# ECR_Schem_1.net
KiCad netlist of a schematic drawn in Altium Designer
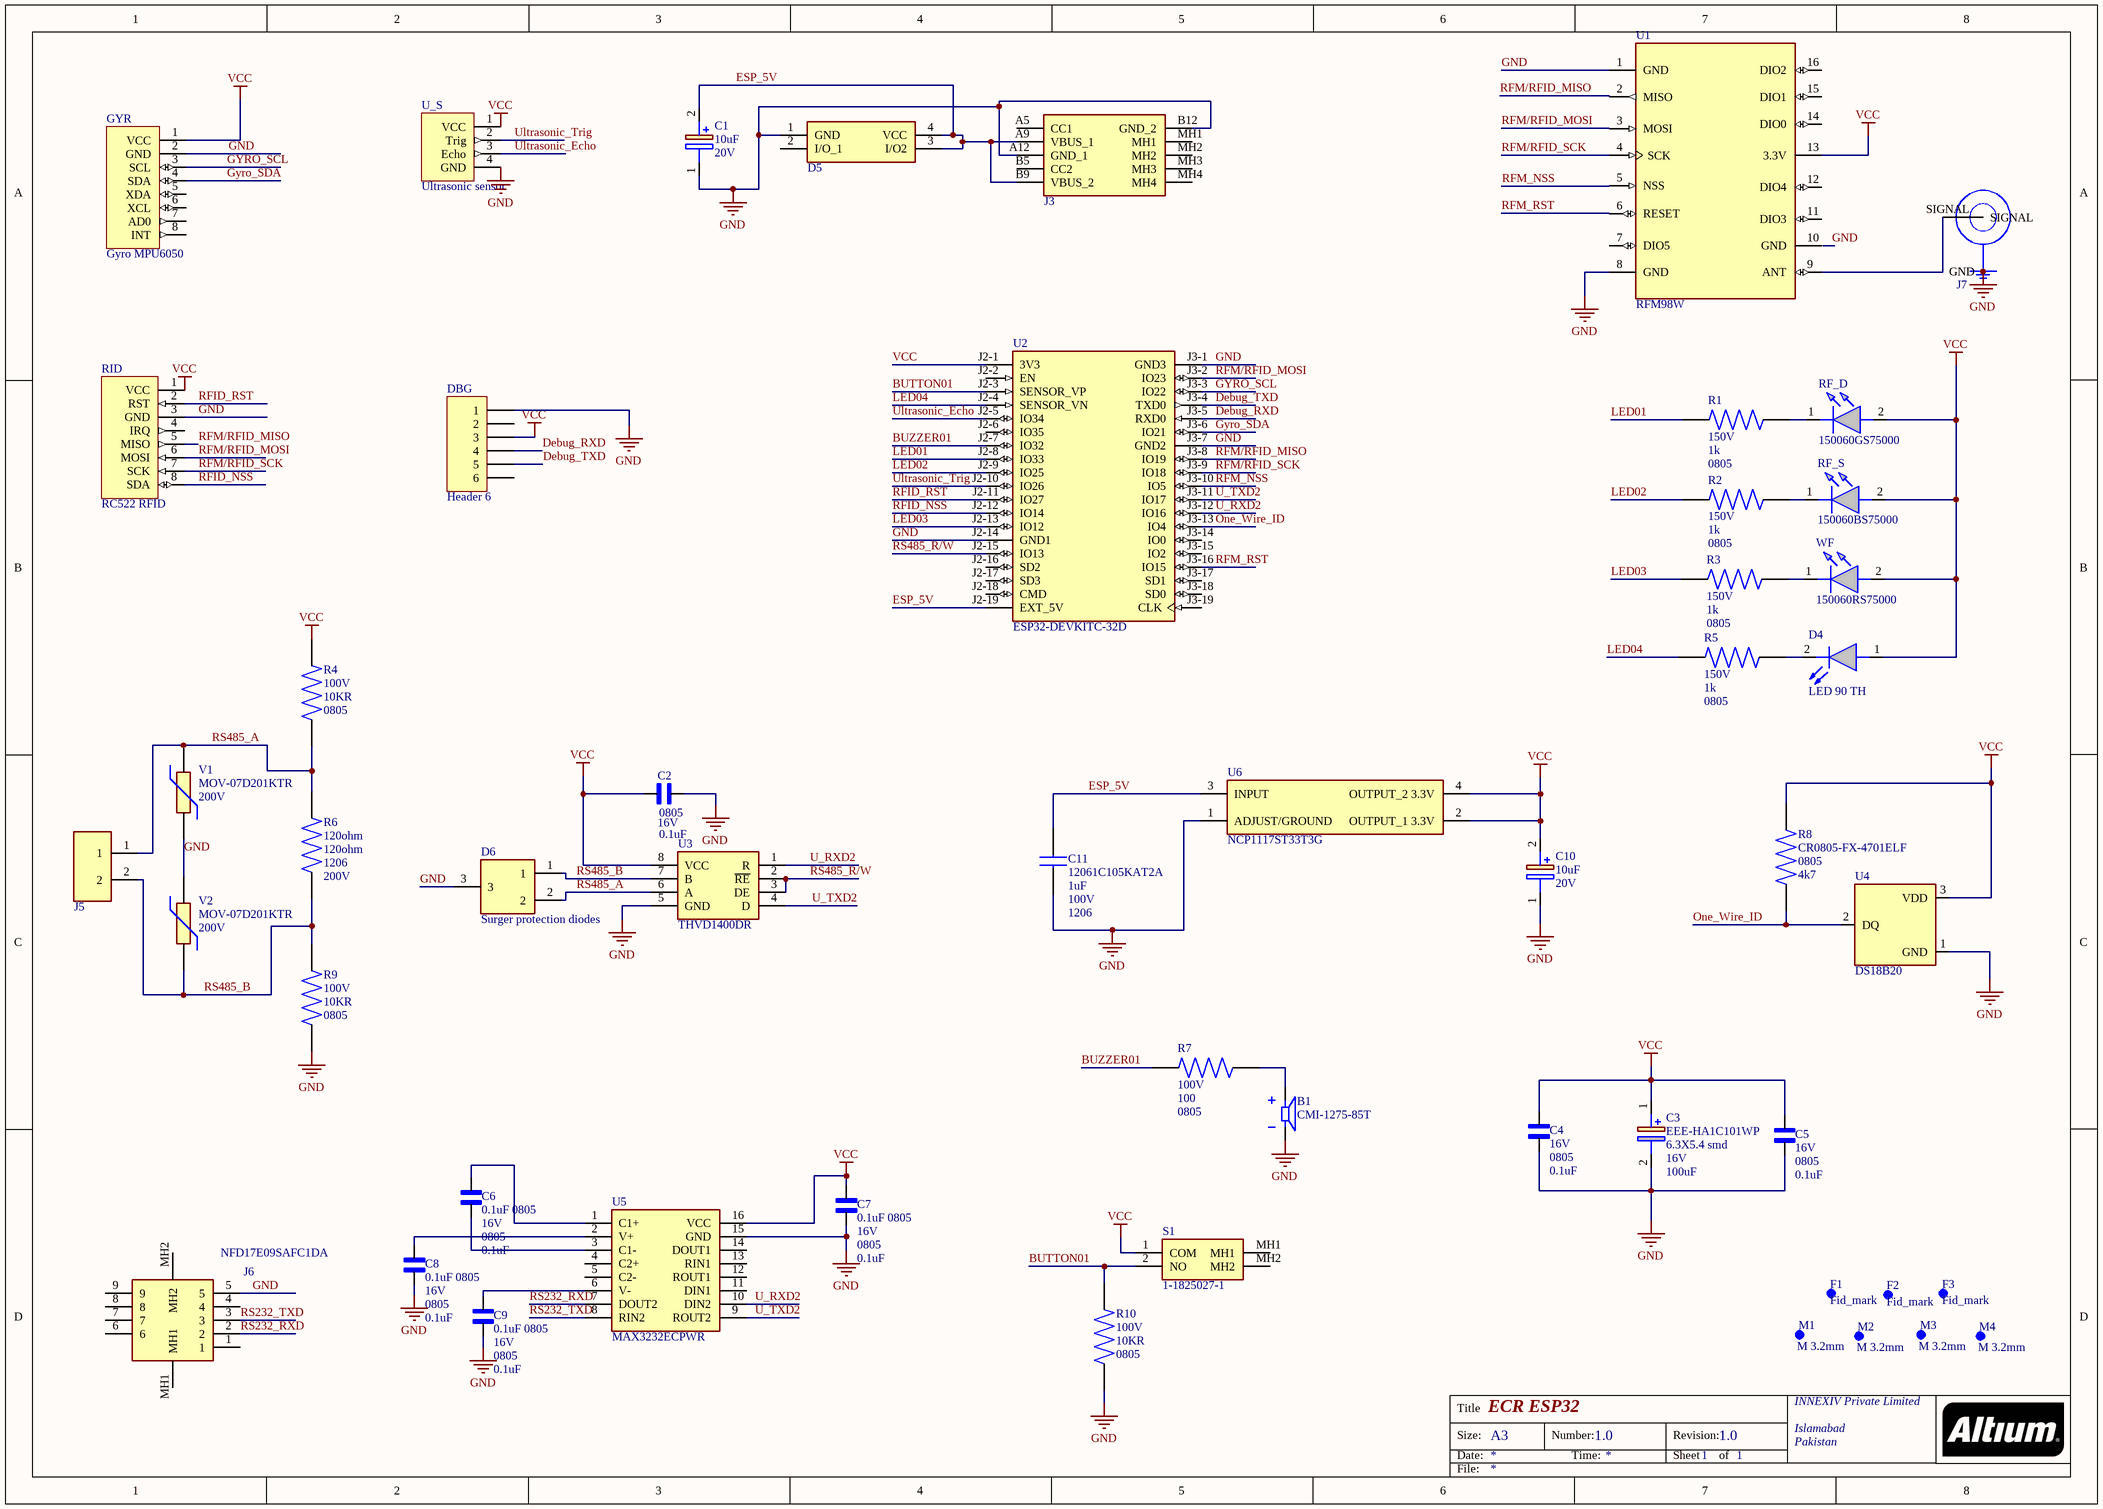
[diagram p0: ECR_Schem_1.SchDoc]

(export (version "E")
  (design (tool "Eeschema 10.0.6"))
  (components
    (comp (ref "B1")
      (value "CMI-1275-85T")
      (footprint "CUI_CMI-1275-85T")
      (description "5V CUI Inc Buzzer")
      (libsource (lib "CMI-1275-85T") (part "CMI-1275-85T"))
    )
    (comp (ref "C1")
      (value "10uF")
      (footprint "CAPPM3528X210N")
      (fields
        (field (name "MANUFACTURER_PART_NUMBER") "TPSB106K020R1000")
        (field (name "MOUSER PART NUMBER") "581-TPSB106K020R1000")
        (field (name "VOLTAGE") "20V")
        (field (name "Comment") "10uF SMD Tantalum")
      )
      (libsource (lib "ECR") (part "TPSB106K020R1000"))
    )
    (comp (ref "C2")
      (value "0.1uF")
      (footprint "CAPC2012X90N")
      (description "Cap Ceramic 0.1uF 16V X7R 5% SMD 0805 125Â°C Paper T/R")
      (fields
        (field (name "MF") "Vishay Vitramon")
        (field (name "MP") "VJ0805Y104JXJPW1BC")
        (field (name "VOLTAGE") "16V")
        (field (name "PACKAGE") "0805")
      )
      (libsource (lib "") (part "VJ0805Y104JXJPW1BC_1"))
    )
    (comp (ref "C3")
      (value "EEE-HA1C101WP")
      (footprint "CAPAE660X800N")
      (description "Cap Aluminum Lytic 100uF 16V 20% (6.3 X 5.4mm) SMD 70mA 1000h 105C Automotive T/R")
      (fields
        (field (name "PACKAGE") "6.3X5.4 smd")
        (field (name "VOLTAGE") "16V")
        (field (name "ALTIUM_VALUE") "100uF")
      )
      (libsource (lib "ECR") (part "EEE-HA1C101WP"))
    )
    (comp (ref "C4")
      (value "0.1uF")
      (footprint "CAPC2012X90N")
      (description "Cap Ceramic 0.1uF 16V X7R 5% SMD 0805 125Â°C Paper T/R")
      (fields
        (field (name "MF") "Vishay Vitramon")
        (field (name "MP") "VJ0805Y104JXJPW1BC")
        (field (name "VOLTAGE") "16V")
        (field (name "PACKAGE") "0805")
      )
      (libsource (lib "ECR") (part "VJ0805Y104JXJPW1BC"))
    )
    (comp (ref "C5")
      (value "0.1uF")
      (footprint "CAPC2012X90N")
      (description "Cap Ceramic 0.1uF 16V X7R 5% SMD 0805 125Â°C Paper T/R")
      (fields
        (field (name "MF") "Vishay Vitramon")
        (field (name "MP") "VJ0805Y104JXJPW1BC")
        (field (name "VOLTAGE") "16V")
        (field (name "PACKAGE") "0805")
      )
      (libsource (lib "ECR") (part "VJ0805Y104JXJPW1BC"))
    )
    (comp (ref "C6")
      (value "0.1uF 0805")
      (footprint "CAPC2012X90N")
      (description "Cap Ceramic 0.1uF 16V X7R 5% SMD 0805 125Â°C Paper T/R")
      (fields
        (field (name "MF") "Vishay Vitramon")
        (field (name "MP") "VJ0805Y104JXJPW1BC")
        (field (name "VOLTAGE") "16V")
        (field (name "PACKAGE") "0805")
        (field (name "ALTIUM_VALUE") "0.1uF")
      )
      (libsource (lib "ECR") (part "VJ0805Y104JXJPW1BC"))
    )
    (comp (ref "C7")
      (value "0.1uF 0805")
      (footprint "CAPC2012X90N")
      (description "Cap Ceramic 0.1uF 16V X7R 5% SMD 0805 125Â°C Paper T/R")
      (fields
        (field (name "MF") "Vishay Vitramon")
        (field (name "MP") "VJ0805Y104JXJPW1BC")
        (field (name "VOLTAGE") "16V")
        (field (name "PACKAGE") "0805")
        (field (name "ALTIUM_VALUE") "0.1uF")
      )
      (libsource (lib "ECR") (part "VJ0805Y104JXJPW1BC"))
    )
    (comp (ref "C8")
      (value "0.1uF 0805")
      (footprint "CAPC2012X90N")
      (description "Cap Ceramic 0.1uF 16V X7R 5% SMD 0805 125Â°C Paper T/R")
      (fields
        (field (name "MF") "Vishay Vitramon")
        (field (name "MP") "VJ0805Y104JXJPW1BC")
        (field (name "VOLTAGE") "16V")
        (field (name "PACKAGE") "0805")
        (field (name "ALTIUM_VALUE") "0.1uF")
      )
      (libsource (lib "ECR") (part "VJ0805Y104JXJPW1BC"))
    )
    (comp (ref "C9")
      (value "0.1uF 0805")
      (footprint "CAPC2012X90N")
      (description "Cap Ceramic 0.1uF 16V X7R 5% SMD 0805 125Â°C Paper T/R")
      (fields
        (field (name "MF") "Vishay Vitramon")
        (field (name "MP") "VJ0805Y104JXJPW1BC")
        (field (name "VOLTAGE") "16V")
        (field (name "PACKAGE") "0805")
        (field (name "ALTIUM_VALUE") "0.1uF")
      )
      (libsource (lib "ECR") (part "VJ0805Y104JXJPW1BC"))
    )
    (comp (ref "C10")
      (value "10uF")
      (footprint "CAPPM3528X210N")
      (fields
        (field (name "MANUFACTURER_PART_NUMBER") "TPSB106K020R1000")
        (field (name "MOUSER PART NUMBER") "581-TPSB106K020R1000")
        (field (name "VOLTAGE") "20V")
        (field (name "Comment") "10uF SMD Tantalum")
      )
      (libsource (lib "ECR") (part "TPSB106K020R1000"))
    )
    (comp (ref "C11")
      (value "12061C105KAT2A")
      (footprint "CAPC3216X229N")
      (fields
        (field (name "MOUSER PART NUMBER") "581-12061C105KAT2A")
        (field (name "ALTIUM_VALUE") "1uF")
        (field (name "VOLTAGE") "100V")
        (field (name "PACKAGE") "1206")
      )
      (libsource (lib "12061C105KAT2A") (part "12061C105KAT2A"))
    )
    (comp (ref "D4")
      (value "LED 90 TH")
      (footprint "HV-31210/260/SUB-U1930")
      (description "HARVATEK 3.0MM ROUND LED LAMP WI")
      (libsource (lib "ECR") (part "HV-31210/260/SUB-U1930"))
    )
    (comp (ref "D5")
      (value "5V fuse USB line")
      (footprint "SR0502CTG")
      (description "LITTELFUSE - SR05-02CTG - DIODE, ESD PROTECTION, 5V, SOT-143")
      (fields
        (field (name "MANUFACTURER_PART_NUMBER") "SR05-02CTG")
        (field (name "MOUSER PART NUMBER") "576-SR05-02CTG")
      )
      (libsource (lib "ECR") (part "SR05-02CTG"))
    )
    (comp (ref "D6")
      (value "Surger protection diodes")
      (footprint "SamacSys:SOT95P230X117-3N")
      (description "Diode")
      (fields
        (field (name "MANUFACTURER_PART_NUMBER") "CDSOT23-SM712")
        (field (name "MOUSER PART NUMBER") "652-CDSOT23-SM712")
      )
      (libsource (lib "ECR") (part "CDSOT23-SM712"))
    )
    (comp (ref "DBG")
      (value "Header 6")
      (footprint "HDR1X6")
      (description "Header, 6-Pin")
      (fields (field (name "PUBLISHER") "Altium Limited"))
      (libsource (lib "Miscellaneous Connectors") (part "Header 6"))
    )
    (comp (ref "F1")
      (value "Fid_mark")
      (footprint "FUP")
      (description "Fiducial_mark")
      (libsource (lib "ECR") (part "Fid_mark"))
    )
    (comp (ref "F2")
      (value "Fid_mark")
      (footprint "FUP")
      (description "Fiducial_mark")
      (libsource (lib "ECR") (part "Fid_mark"))
    )
    (comp (ref "F3")
      (value "Fid_mark")
      (footprint "FUP")
      (description "Fiducial_mark")
      (libsource (lib "ECR") (part "Fid_mark"))
    )
    (comp (ref "GYR")
      (value "Gyro MPU6050")
      (footprint "MPU_8pin")
      (description "MPU_6050\r\nGyroscope")
      (libsource (lib "ECR") (part "MPU_6050"))
    )
    (comp (ref "J3")
      (value "USB Type C PCB")
      (footprint "USB4125GFA")
      (fields
        (field (name "MANUFACTURER_PART_NUMBER") "USB4125-GF-A")
        (field (name "MOUSER PART NUMBER") "640-USB4125-GF-A")
      )
      (libsource (lib "ECR") (part "USB4125-GF-A"))
    )
    (comp (ref "J5")
      (value "3.81mm wire to pcb")
      (footprint "1728284 3.81 wire to pcb")
      (description "TERM BLOCK 2POS 55DEG 3.81MM PCB")
      (fields (field (name "MANUFACTURER") "Phoenix contact"))
      (libsource (lib "ECR") (part "1728284 terminal block 3.81"))
    )
    (comp (ref "J6")
      (value "NFD17E09SAFC1DA")
      (footprint "NFD17E09SAFC1DA")
      (description "D-Sub, 9 Pin Socket, Right Angle, Boardlocks #4-40 UNC Threaded Hole")
      (libsource (lib "NFD17E09SAFC1DA") (part "NFD17E09SAFC1DA"))
    )
    (comp (ref "J7")
      (value "IPEX antenna connector PCB")
      (footprint "AMPHENOL_A-1JB")
      (description "AMC IPEX Straight PCB Jack, Surface Mount, 2500 pc Reel, 50 Ohm")
      (fields (field (name "MP") "A-1JB"))
      (libsource (lib "A-1JB") (part "A-1JB"))
    )
    (comp (ref "M1")
      (value "M 3.2mm")
      (footprint "Screw Hole 3.2mm")
      (description "PCB Munting Hole 3.2mm")
      (libsource (lib "ECR") (part "Munting Hole 3.2mm"))
    )
    (comp (ref "M2")
      (value "M 3.2mm")
      (footprint "Screw Hole 3.2mm")
      (description "PCB Munting Hole 3.2mm")
      (libsource (lib "ECR") (part "Munting Hole 3.2mm"))
    )
    (comp (ref "M3")
      (value "M 3.2mm")
      (footprint "Screw Hole 3.2mm")
      (description "PCB Munting Hole 3.2mm")
      (libsource (lib "ECR") (part "Munting Hole 3.2mm"))
    )
    (comp (ref "M4")
      (value "M 3.2mm")
      (footprint "Screw Hole 3.2mm")
      (description "PCB Munting Hole 3.2mm")
      (libsource (lib "ECR") (part "Munting Hole 3.2mm"))
    )
    (comp (ref "R1")
      (value "1k")
      (footprint "0805_RESC2012X50N")
      (description "Thick Film Resistors - SMD 1 k Ohms 125mW 0805 5% AEC-Q200 Standard Power Version")
      (fields
        (field (name "MF") "{'manufacturer': u'Bourns'}")
        (field (name "MP") "AC0805JR-071KL")
        (field (name "VOLTAGE") "150V")
        (field (name "PACKAGE") "0805")
      )
      (libsource (lib "ECR") (part "AC0805JR-071KL"))
    )
    (comp (ref "R2")
      (value "1k")
      (footprint "0805_RESC2012X50N")
      (description "Thick Film Resistors - SMD 1 k Ohms 125mW 0805 5% AEC-Q200 Standard Power Version")
      (fields
        (field (name "MF") "{'manufacturer': u'Bourns'}")
        (field (name "MP") "AC0805JR-071KL")
        (field (name "VOLTAGE") "150V")
        (field (name "PACKAGE") "0805")
      )
      (libsource (lib "ECR") (part "AC0805JR-071KL"))
    )
    (comp (ref "R3")
      (value "1k")
      (footprint "0805_RESC2012X50N")
      (description "Thick Film Resistors - SMD 1 k Ohms 125mW 0805 5% AEC-Q200 Standard Power Version")
      (fields
        (field (name "MF") "{'manufacturer': u'Bourns'}")
        (field (name "MP") "AC0805JR-071KL")
        (field (name "VOLTAGE") "150V")
        (field (name "PACKAGE") "0805")
      )
      (libsource (lib "ECR") (part "AC0805JR-071KL"))
    )
    (comp (ref "R4")
      (value "10KR")
      (footprint "0805_RESC2012X50N")
      (fields
        (field (name "MF") "{'manufacturer': u'Bourns'}")
        (field (name "MP") "CR0805-FX-1002ELF")
        (field (name "VOLTAGE") "100V")
        (field (name "PACKAGE") "0805")
        (field (name "Comment") "10K 0805")
      )
      (libsource (lib "ECR") (part "CR0805-FX-1002ELF"))
    )
    (comp (ref "R5")
      (value "1k")
      (footprint "0805_RESC2012X50N")
      (description "Thick Film Resistors - SMD 1 k Ohms 125mW 0805 5% AEC-Q200 Standard Power Version")
      (fields
        (field (name "MF") "{'manufacturer': u'Bourns'}")
        (field (name "MP") "AC0805JR-071KL")
        (field (name "VOLTAGE") "150V")
        (field (name "PACKAGE") "0805")
      )
      (libsource (lib "ECR") (part "AC0805JR-071KL"))
    )
    (comp (ref "R6")
      (value "120ohm")
      (footprint "1206_RESC3216X06N")
      (description "RES 120 OHM 5% 1/4W 1206")
      (fields
        (field (name "PART NUMBER") "WR12X1002FTL")
        (field (name "ALTIUM_VALUE") "120ohm")
        (field (name "PACKAGE") "1206")
        (field (name "VOLTAGE") "200V")
      )
      (libsource (lib "ECR") (part "WR12X1002FTL"))
    )
    (comp (ref "R7")
      (value "100")
      (footprint "0805_RESC2012X50N")
      (description "Thick Film Resistors - SMD 0805 100ohms 0.5W 5% Tolerance")
      (fields
        (field (name "MF") "{'manufacturer': u'Bourns'}")
        (field (name "MP") "ERJ-P06J101V")
        (field (name "VOLTAGE") "100V")
        (field (name "PACKAGE") "0805")
      )
      (libsource (lib "ECR") (part "ERJ-P06J101V"))
    )
    (comp (ref "R8")
      (value "CR0805-FX-4701ELF")
      (footprint "0805_RESC2012X50N")
      (description "BOURNS - CR0805-FX-4701ELF - RES, THICK FILM, 4K7, 1%, 0.125W, 0805")
      (fields
        (field (name "MOUSER PART NUMBER") "652-CR0805FX-4701ELF")
        (field (name "PACKAGE") "0805")
        (field (name "ALTIUM_VALUE") "4k7")
      )
      (libsource (lib "ECR") (part "CR0805-FX-4701ELF"))
    )
    (comp (ref "R9")
      (value "10KR")
      (footprint "0805_RESC2012X50N")
      (fields
        (field (name "MF") "{'manufacturer': u'Bourns'}")
        (field (name "MP") "CR0805-FX-1002ELF")
        (field (name "VOLTAGE") "100V")
        (field (name "PACKAGE") "0805")
        (field (name "Comment") "10K 0805")
      )
      (libsource (lib "ECR") (part "CR0805-FX-1002ELF"))
    )
    (comp (ref "R10")
      (value "10KR")
      (footprint "0805_RESC2012X50N")
      (fields
        (field (name "MF") "{'manufacturer': u'Bourns'}")
        (field (name "MP") "CR0805-FX-1002ELF")
        (field (name "VOLTAGE") "100V")
        (field (name "PACKAGE") "0805")
        (field (name "Comment") "10K 0805")
      )
      (libsource (lib "ECR") (part "CR0805-FX-1002ELF"))
    )
    (comp (ref "RF_D")
      (value "150060GS75000")
      (footprint "LEDC1608X80N")
      (description "Wurth Elektronik WL-SMCW 520 nm Green LED, 1608 (0603) Clear SMD package")
      (fields (field (name "MOUSER PART NUMBER") "710-150060GS75000"))
      (libsource (lib "150060GS75000") (part "150060GS75000"))
    )
    (comp (ref "RF_S")
      (value "150060BS75000")
      (footprint "LEDC1608X80N")
      (fields (field (name "MOUSER PART NUMBER") "710-150060BS75000"))
      (libsource (lib "150060BS75000") (part "150060BS75000"))
    )
    (comp (ref "RID")
      (value "RC522 RFID")
      (footprint "RFID_8pin")
      (description "RFID card reader")
      (libsource (lib "ECR") (part "RFID-RC522"))
    )
    (comp (ref "S1")
      (value "1-1825027-1")
      (footprint "118250271")
      (description "Black Button Tactile Switch, Single Pole Single Throw (SPST) 50 mA @ 24 V dc 5.74mm")
      (libsource (lib "1-1825027-1") (part "1-1825027-1"))
    )
    (comp (ref "U1")
      (value "RFM98W")
      (footprint "XCVR_RFM98W-433S2")
      (description "802.15.4, General ISM < 1GHz LoRaâ„¢ Transceiver Module 433MHz Surface Mount")
      (fields (field (name "MF") "RF Solutions") (field (name "MP") "RFM98W-433S2"))
      (libsource (lib "RFM98W") (part "RFM98W"))
    )
    (comp (ref "U2")
      (value "ESP32-DEVKITC-32D")
      (footprint "MODULE_ESP32-DEVKITC-32D")
      (description "WiFi Development Tools (802.11) ESP32 General Development Kit, ESP32-WROOM-32D on the board")
      (fields (field (name "MF") "Espressif Systems"))
      (libsource (lib "ESP32-DEVKITC-32D") (part "ESP32-DEVKITC-32D"))
    )
    (comp (ref "U3")
      (value "THVD1400DR")
      (footprint "SOIC127P600X175-8N")
      (fields (field (name "MOUSER PART NUMBER") "595-THVD1400DR"))
      (libsource (lib "THVD1400DR") (part "THVD1400DR"))
    )
    (comp (ref "U4")
      (value "DS18B20")
      (footprint "TO-92-TO92127P495H2044-3")
      (description "Temperature Sensor Digital, Local -55Â°C ~ 125Â°C 12 b 8-uMAX-EP¦8-uSOP-EP")
      (fields (field (name "MF") "Maxim"))
      (libsource (lib "DS18B20") (part "DS18B20"))
    )
    (comp (ref "U5")
      (value "MAX3232ECPWR")
      (footprint "SOP65P640X120-16N")
      (description "3-V to 5.5-V multichannel RS-232 line driver and receiver with +/-15-kV IEC ESD protection")
      (fields (field (name "MOUSER PART NUMBER") "595-MAX3232ECPWR"))
      (libsource (lib "MAX3232ECPWR") (part "MAX3232ECPWR"))
    )
    (comp (ref "U6")
      (value "NCP1117ST33T3G")
      (footprint "SOT230P700X180-4N")
      (description "ON SEMICONDUCTOR - NCP1117ST33T3G - IC, LINEAR VOLTAGE REGULATOR")
      (fields (field (name "MOUSER PART NUMBER") "863-NCP1117ST33T3G"))
      (libsource (lib "NCP1117ST33T3G") (part "NCP1117ST33T3G"))
    )
    (comp (ref "U_S")
      (value "Ultrasonic sensor")
      (footprint "UltraSonic 4 Pins")
      (description "Hc Sr04 Arduino Ultrasonic Sensor")
      (libsource (lib "ECR") (part "HC-SR04"))
    )
    (comp (ref "V1")
      (value "MOV-07D201KTR")
      (footprint "MOV07D201KTR")
      (description "VARISTOR 200V 1.2KA DISC 7MM")
      (fields (field (name "MOUSER PART NUMBER") "652-MOV-07D201KTR") (field (name "VOLTAGE") "200V"))
      (libsource (lib "ECR") (part "MOV-07D201KTR"))
    )
    (comp (ref "V2")
      (value "MOV-07D201KTR")
      (footprint "MOV07D201KTR")
      (description "VARISTOR 200V 1.2KA DISC 7MM")
      (fields (field (name "MOUSER PART NUMBER") "652-MOV-07D201KTR") (field (name "VOLTAGE") "200V"))
      (libsource (lib "ECR") (part "MOV-07D201KTR"))
    )
    (comp (ref "WF")
      (value "150060RS75000")
      (footprint "LEDC1608X80N")
      (description "WURTH ELEKTRONIK - 150060RS75000 - LED, 0603, RED, 250MCD, 625NM")
      (fields (field (name "MOUSER PART NUMBER") "710-150060RS75000"))
      (libsource (lib "150060RS75000") (part "150060RS75000"))
    )
  )
  (nets
    (net (code "1") (name "/BUTTON01") (class "Default")
      (node (ref "R10") (pin "2") (pinfunction "2_2") (pintype "passive"))
      (node (ref "S1") (pin "2") (pinfunction "NO_2") (pintype "passive"))
      (node (ref "U2") (pin "J2-3") (pinfunction "SENSOR_VP_J2-3") (pintype "input"))
    )
    (net (code "2") (name "/BUZZER01") (class "Default")
      (node (ref "R7") (pin "1") (pinfunction "1_1") (pintype "passive"))
      (node (ref "U2") (pin "J2-7") (pinfunction "IO32_J2-7") (pintype "bidirectional"))
    )
    (net (code "3") (name "/Debug_RXD") (class "Default")
      (node (ref "DBG") (pin "4") (pinfunction "4_4") (pintype "passive"))
      (node (ref "U2") (pin "J3-5") (pinfunction "RXD0_J3-5") (pintype "input"))
    )
    (net (code "4") (name "/Debug_TXD") (class "Default")
      (node (ref "DBG") (pin "5") (pinfunction "5_5") (pintype "passive"))
      (node (ref "U2") (pin "J3-4") (pinfunction "TXD0_J3-4") (pintype "output"))
    )
    (net (code "5") (name "/ESP_5V") (class "Default")
      (node (ref "C1") (pin "2") (pinfunction "2_2") (pintype "passive"))
      (node (ref "C11") (pin "2") (pinfunction "2_2") (pintype "passive"))
      (node (ref "D5") (pin "3") (pinfunction "I/O2_3") (pintype "passive"))
      (node (ref "D5") (pin "4") (pinfunction "VCC_4") (pintype "passive"))
      (node (ref "J3") (pin "A9") (pinfunction "VBUS_1_A9") (pintype "passive"))
      (node (ref "J3") (pin "B9") (pinfunction "VBUS_2_B9") (pintype "passive"))
      (node (ref "U2") (pin "J2-19") (pinfunction "EXT_5V_J2-19") (pintype "power_in"))
      (node (ref "U6") (pin "3") (pinfunction "INPUT_3") (pintype "passive"))
    )
    (net (code "6") (name "/GYRO_SCL") (class "Default")
      (node (ref "GYR") (pin "3") (pinfunction "SCL_3") (pintype "bidirectional"))
      (node (ref "U2") (pin "J3-3") (pinfunction "IO22_J3-3") (pintype "bidirectional"))
    )
    (net (code "7") (name "/Gyro_SDA") (class "Default")
      (node (ref "GYR") (pin "4") (pinfunction "SDA_4") (pintype "bidirectional"))
      (node (ref "U2") (pin "J3-6") (pinfunction "IO21_J3-6") (pintype "bidirectional"))
    )
    (net (code "8") (name "/LED01") (class "Default")
      (node (ref "R1") (pin "1") (pinfunction "1_1") (pintype "passive"))
      (node (ref "U2") (pin "J2-8") (pinfunction "IO33_J2-8") (pintype "bidirectional"))
    )
    (net (code "9") (name "/LED02") (class "Default")
      (node (ref "R2") (pin "1") (pinfunction "1_1") (pintype "passive"))
      (node (ref "U2") (pin "J2-9") (pinfunction "IO25_J2-9") (pintype "bidirectional"))
    )
    (net (code "10") (name "/LED03") (class "Default")
      (node (ref "R3") (pin "1") (pinfunction "1_1") (pintype "passive"))
      (node (ref "U2") (pin "J2-13") (pinfunction "IO12_J2-13") (pintype "bidirectional"))
    )
    (net (code "11") (name "/LED04") (class "Default")
      (node (ref "R5") (pin "1") (pinfunction "1_1") (pintype "passive"))
      (node (ref "U2") (pin "J2-4") (pinfunction "SENSOR_VN_J2-4") (pintype "input"))
    )
    (net (code "12") (name "/One_Wire_ID") (class "Default")
      (node (ref "R8") (pin "1") (pinfunction "1_1") (pintype "passive"))
      (node (ref "U2") (pin "J3-13") (pinfunction "IO4_J3-13") (pintype "bidirectional"))
      (node (ref "U4") (pin "2") (pinfunction "DQ_2") (pintype "bidirectional"))
    )
    (net (code "13") (name "/RFID_NSS") (class "Default")
      (node (ref "RID") (pin "8") (pinfunction "SDA_8") (pintype "bidirectional"))
      (node (ref "U2") (pin "J2-12") (pinfunction "IO14_J2-12") (pintype "bidirectional"))
    )
    (net (code "14") (name "/RFID_RST") (class "Default")
      (node (ref "RID") (pin "2") (pinfunction "RST_2") (pintype "input"))
      (node (ref "U2") (pin "J2-11") (pinfunction "IO27_J2-11") (pintype "bidirectional"))
    )
    (net (code "15") (name "/RFM_NSS") (class "Default")
      (node (ref "U1") (pin "5") (pinfunction "NSS_5") (pintype "input"))
      (node (ref "U2") (pin "J3-10") (pinfunction "IO5_J3-10") (pintype "bidirectional"))
    )
    (net (code "16") (name "/RFM_RST") (class "Default")
      (node (ref "U1") (pin "6") (pinfunction "RESET_6") (pintype "bidirectional"))
      (node (ref "U2") (pin "J3-16") (pinfunction "IO15_J3-16") (pintype "bidirectional"))
    )
    (net (code "17") (name "/RFM{slash}RFID_MISO") (class "Default")
      (node (ref "RID") (pin "5") (pinfunction "MISO_5") (pintype "output"))
      (node (ref "U1") (pin "2") (pinfunction "MISO_2") (pintype "output"))
      (node (ref "U2") (pin "J3-8") (pinfunction "IO19_J3-8") (pintype "bidirectional"))
    )
    (net (code "18") (name "/RFM{slash}RFID_MOSI") (class "Default")
      (node (ref "RID") (pin "6") (pinfunction "MOSI_6") (pintype "input"))
      (node (ref "U1") (pin "3") (pinfunction "MOSI_3") (pintype "input"))
      (node (ref "U2") (pin "J3-2") (pinfunction "IO23_J3-2") (pintype "bidirectional"))
    )
    (net (code "19") (name "/RFM{slash}RFID_SCK") (class "Default")
      (node (ref "RID") (pin "7") (pinfunction "SCK_7") (pintype "input"))
      (node (ref "U1") (pin "4") (pinfunction "SCK_4") (pintype "input"))
      (node (ref "U2") (pin "J3-9") (pinfunction "IO18_J3-9") (pintype "bidirectional"))
    )
    (net (code "20") (name "/RS232_RXD") (class "Default")
      (node (ref "J6") (pin "2") (pinfunction "2_2") (pintype "passive"))
      (node (ref "U5") (pin "7") (pinfunction "DOUT2_7") (pintype "passive"))
    )
    (net (code "21") (name "/RS232_TXD") (class "Default")
      (node (ref "J6") (pin "3") (pinfunction "3_3") (pintype "passive"))
      (node (ref "U5") (pin "8") (pinfunction "RIN2_8") (pintype "passive"))
    )
    (net (code "22") (name "/RS485_A") (class "Default")
      (node (ref "D6") (pin "2") (pinfunction "2_2") (pintype "passive"))
      (node (ref "J5") (pin "1") (pinfunction "1_1") (pintype "passive"))
      (node (ref "R4") (pin "1") (pinfunction "1_1") (pintype "passive"))
      (node (ref "R6") (pin "2") (pinfunction "2_2") (pintype "passive"))
      (node (ref "U3") (pin "6") (pinfunction "A_6") (pintype "passive"))
      (node (ref "V1") (pin "2") (pinfunction "2_2") (pintype "passive"))
    )
    (net (code "23") (name "/RS485_B") (class "Default")
      (node (ref "D6") (pin "1") (pinfunction "1_1") (pintype "passive"))
      (node (ref "J5") (pin "2") (pinfunction "2_2") (pintype "passive"))
      (node (ref "R6") (pin "1") (pinfunction "1_1") (pintype "passive"))
      (node (ref "R9") (pin "2") (pinfunction "2_2") (pintype "passive"))
      (node (ref "U3") (pin "7") (pinfunction "B_7") (pintype "passive"))
      (node (ref "V2") (pin "1") (pinfunction "1_1") (pintype "passive"))
    )
    (net (code "24") (name "/RS485_R{slash}W") (class "Default")
      (node (ref "U2") (pin "J2-15") (pinfunction "IO13_J2-15") (pintype "bidirectional"))
      (node (ref "U3") (pin "2") (pinfunction "~{RE}_2") (pintype "passive"))
      (node (ref "U3") (pin "3") (pinfunction "DE_3") (pintype "passive"))
    )
    (net (code "25") (name "/U_RXD2") (class "Default")
      (node (ref "U2") (pin "J3-12") (pinfunction "IO16_J3-12") (pintype "bidirectional"))
      (node (ref "U3") (pin "1") (pinfunction "R_1") (pintype "passive"))
      (node (ref "U5") (pin "10") (pinfunction "DIN2_10") (pintype "passive"))
    )
    (net (code "26") (name "/U_TXD2") (class "Default")
      (node (ref "U2") (pin "J3-11") (pinfunction "IO17_J3-11") (pintype "bidirectional"))
      (node (ref "U3") (pin "4") (pinfunction "D_4") (pintype "passive"))
      (node (ref "U5") (pin "9") (pinfunction "ROUT2_9") (pintype "passive"))
    )
    (net (code "27") (name "/Ultrasonic_Echo") (class "Default")
      (node (ref "U2") (pin "J2-5") (pinfunction "IO34_J2-5") (pintype "bidirectional"))
      (node (ref "U_S") (pin "3") (pinfunction "Echo_3") (pintype "output"))
    )
    (net (code "28") (name "/Ultrasonic_Trig") (class "Default")
      (node (ref "U2") (pin "J2-10") (pinfunction "IO26_J2-10") (pintype "bidirectional"))
      (node (ref "U_S") (pin "2") (pinfunction "Trig_2") (pintype "output"))
    )
    (net (code "29") (name "GND") (class "Default")
      (node (ref "B1") (pin "N") (pinfunction "N_N") (pintype "passive"))
      (node (ref "C1") (pin "1") (pinfunction "1_1") (pintype "passive"))
      (node (ref "C10") (pin "1") (pinfunction "1_1") (pintype "passive"))
      (node (ref "C11") (pin "1") (pinfunction "1_1") (pintype "passive"))
      (node (ref "C2") (pin "2") (pinfunction "2_2") (pintype "passive"))
      (node (ref "C3") (pin "2") (pinfunction "-_2") (pintype "passive"))
      (node (ref "C4") (pin "1") (pinfunction "1_1") (pintype "passive"))
      (node (ref "C5") (pin "1") (pinfunction "1_1") (pintype "passive"))
      (node (ref "C7") (pin "1") (pinfunction "1_1") (pintype "passive"))
      (node (ref "C8") (pin "1") (pinfunction "1_1") (pintype "passive"))
      (node (ref "C9") (pin "1") (pinfunction "1_1") (pintype "passive"))
      (node (ref "D5") (pin "1") (pinfunction "GND_1") (pintype "passive"))
      (node (ref "D6") (pin "3") (pinfunction "3_3") (pintype "passive"))
      (node (ref "DBG") (pin "1") (pinfunction "1_1") (pintype "passive"))
      (node (ref "GYR") (pin "2") (pinfunction "GND_2") (pintype "power_in"))
      (node (ref "J3") (pin "A12") (pinfunction "GND_1_A12") (pintype "passive"))
      (node (ref "J3") (pin "B12") (pinfunction "GND_2_B12") (pintype "passive"))
      (node (ref "J6") (pin "5") (pinfunction "5_5") (pintype "passive"))
      (node (ref "J7") (pin "GND1") (pinfunction "GND_GND1") (pintype "passive"))
      (node (ref "J7") (pin "GND2") (pinfunction "GND_GND2") (pintype "passive"))
      (node (ref "J7") (pin "OPTIONAL_GND") (pinfunction "GND_OPTIONAL_GND") (pintype "passive"))
      (node (ref "R10") (pin "1") (pinfunction "1_1") (pintype "passive"))
      (node (ref "R9") (pin "1") (pinfunction "1_1") (pintype "passive"))
      (node (ref "RID") (pin "3") (pinfunction "GND_3") (pintype "power_in"))
      (node (ref "U1") (pin "1") (pinfunction "GND_1") (pintype "power_in"))
      (node (ref "U1") (pin "8") (pinfunction "GND_8") (pintype "power_in"))
      (node (ref "U2") (pin "J2-14") (pinfunction "GND1_J2-14") (pintype "power_in"))
      (node (ref "U2") (pin "J3-1") (pinfunction "GND3_J3-1") (pintype "power_in"))
      (node (ref "U2") (pin "J3-7") (pinfunction "GND2_J3-7") (pintype "power_in"))
      (node (ref "U3") (pin "5") (pinfunction "GND_5") (pintype "passive"))
      (node (ref "U4") (pin "1") (pinfunction "GND_1") (pintype "power_in"))
      (node (ref "U5") (pin "15") (pinfunction "GND_15") (pintype "passive"))
      (node (ref "U6") (pin "1") (pinfunction "ADJUST/GROUND_1") (pintype "passive"))
      (node (ref "U_S") (pin "4") (pinfunction "GND_4") (pintype "power_in"))
      (node (ref "V1") (pin "1") (pinfunction "1_1") (pintype "passive"))
      (node (ref "V2") (pin "2") (pinfunction "2_2") (pintype "passive"))
    )
    (net (code "30") (name "Net-(B1-PadP)") (class "Default")
      (node (ref "B1") (pin "P") (pinfunction "P_P") (pintype "passive"))
      (node (ref "R7") (pin "2") (pinfunction "2_2") (pintype "passive"))
    )
    (net (code "31") (name "Net-(D4-K)") (class "Default")
      (node (ref "D4") (pin "2") (pinfunction "K_2") (pintype "passive"))
      (node (ref "R5") (pin "2") (pinfunction "2_2") (pintype "passive"))
    )
    (net (code "32") (name "Net-(RF_D-K)") (class "Default")
      (node (ref "R1") (pin "2") (pinfunction "2_2") (pintype "passive"))
      (node (ref "RF_D") (pin "1") (pinfunction "K_1") (pintype "passive"))
    )
    (net (code "33") (name "Net-(RF_S-K)") (class "Default")
      (node (ref "R2") (pin "2") (pinfunction "2_2") (pintype "passive"))
      (node (ref "RF_S") (pin "1") (pinfunction "K_1") (pintype "passive"))
    )
    (net (code "34") (name "Net-(U1-ANT)") (class "Default")
      (node (ref "J7") (pin "SIGNAL") (pinfunction "SIGNAL_SIGNAL") (pintype "passive"))
      (node (ref "U1") (pin "9") (pinfunction "ANT_9") (pintype "bidirectional"))
    )
    (net (code "35") (name "Net-(U5-C1+)") (class "Default")
      (node (ref "C6") (pin "2") (pinfunction "2_2") (pintype "passive"))
      (node (ref "U5") (pin "1") (pinfunction "C1+_1") (pintype "passive"))
    )
    (net (code "36") (name "Net-(U5-C1-)") (class "Default")
      (node (ref "C6") (pin "1") (pinfunction "1_1") (pintype "passive"))
      (node (ref "U5") (pin "3") (pinfunction "C1-_3") (pintype "passive"))
    )
    (net (code "37") (name "Net-(U5-V+)") (class "Default")
      (node (ref "C8") (pin "2") (pinfunction "2_2") (pintype "passive"))
      (node (ref "U5") (pin "2") (pinfunction "V+_2") (pintype "passive"))
    )
    (net (code "38") (name "Net-(U5-V-)") (class "Default")
      (node (ref "C9") (pin "2") (pinfunction "2_2") (pintype "passive"))
      (node (ref "U5") (pin "6") (pinfunction "V-_6") (pintype "passive"))
    )
    (net (code "39") (name "Net-(WF-K)") (class "Default")
      (node (ref "R3") (pin "2") (pinfunction "2_2") (pintype "passive"))
      (node (ref "WF") (pin "1") (pinfunction "K_1") (pintype "passive"))
    )
    (net (code "40") (name "VCC") (class "Default")
      (node (ref "C10") (pin "2") (pinfunction "2_2") (pintype "passive"))
      (node (ref "C2") (pin "1") (pinfunction "1_1") (pintype "passive"))
      (node (ref "C3") (pin "1") (pinfunction "+_1") (pintype "passive"))
      (node (ref "C4") (pin "2") (pinfunction "2_2") (pintype "passive"))
      (node (ref "C5") (pin "2") (pinfunction "2_2") (pintype "passive"))
      (node (ref "C7") (pin "2") (pinfunction "2_2") (pintype "passive"))
      (node (ref "D4") (pin "1") (pinfunction "A_1") (pintype "passive"))
      (node (ref "DBG") (pin "3") (pinfunction "3_3") (pintype "passive"))
      (node (ref "GYR") (pin "1") (pinfunction "VCC_1") (pintype "power_in"))
      (node (ref "R4") (pin "2") (pinfunction "2_2") (pintype "passive"))
      (node (ref "R8") (pin "2") (pinfunction "2_2") (pintype "passive"))
      (node (ref "RF_D") (pin "2") (pinfunction "A_2") (pintype "passive"))
      (node (ref "RF_S") (pin "2") (pinfunction "A_2") (pintype "passive"))
      (node (ref "RID") (pin "1") (pinfunction "VCC_1") (pintype "power_in"))
      (node (ref "S1") (pin "1") (pinfunction "COM_1") (pintype "passive"))
      (node (ref "U1") (pin "13") (pinfunction "3.3V_13") (pintype "power_in"))
      (node (ref "U2") (pin "J2-1") (pinfunction "3V3_J2-1") (pintype "power_in"))
      (node (ref "U3") (pin "8") (pinfunction "VCC_8") (pintype "passive"))
      (node (ref "U4") (pin "3") (pinfunction "VDD_3") (pintype "power_in"))
      (node (ref "U5") (pin "16") (pinfunction "VCC_16") (pintype "passive"))
      (node (ref "U6") (pin "2") (pinfunction "OUTPUT_1_3.3V_2") (pintype "passive"))
      (node (ref "U6") (pin "4") (pinfunction "OUTPUT_2_3.3V_4") (pintype "passive"))
      (node (ref "U_S") (pin "1") (pinfunction "VCC_1") (pintype "power_in"))
      (node (ref "WF") (pin "2") (pinfunction "A_2") (pintype "passive"))
    )
    (net (code "41") (name "unconnected-(D5-I{slash}O_1-Pad2)") (class "Default")
      (node (ref "D5") (pin "2") (pinfunction "I/O_1_2") (pintype "passive"))
    )
    (net (code "42") (name "unconnected-(DBG-Pad2)") (class "Default")
      (node (ref "DBG") (pin "2") (pinfunction "2_2") (pintype "passive"))
    )
    (net (code "43") (name "unconnected-(DBG-Pad6)") (class "Default")
      (node (ref "DBG") (pin "6") (pinfunction "6_6") (pintype "passive"))
    )
    (net (code "44") (name "unconnected-(GYR-AD0-Pad7)") (class "Default")
      (node (ref "GYR") (pin "7") (pinfunction "AD0_7") (pintype "output"))
    )
    (net (code "45") (name "unconnected-(GYR-INT-Pad8)") (class "Default")
      (node (ref "GYR") (pin "8") (pinfunction "INT_8") (pintype "output"))
    )
    (net (code "46") (name "unconnected-(GYR-XCL-Pad6)") (class "Default")
      (node (ref "GYR") (pin "6") (pinfunction "XCL_6") (pintype "bidirectional"))
    )
    (net (code "47") (name "unconnected-(GYR-XDA-Pad5)") (class "Default")
      (node (ref "GYR") (pin "5") (pinfunction "XDA_5") (pintype "bidirectional"))
    )
    (net (code "48") (name "unconnected-(J3-CC1-PadA5)") (class "Default")
      (node (ref "J3") (pin "A5") (pinfunction "CC1_A5") (pintype "passive"))
    )
    (net (code "49") (name "unconnected-(J3-CC2-PadB5)") (class "Default")
      (node (ref "J3") (pin "B5") (pinfunction "CC2_B5") (pintype "passive"))
    )
    (net (code "50") (name "unconnected-(J3-PadMH1)") (class "Default")
      (node (ref "J3") (pin "MH1") (pinfunction "MH1_MH1") (pintype "passive"))
    )
    (net (code "51") (name "unconnected-(J3-PadMH2)") (class "Default")
      (node (ref "J3") (pin "MH2") (pinfunction "MH2_MH2") (pintype "passive"))
    )
    (net (code "52") (name "unconnected-(J3-PadMH3)") (class "Default")
      (node (ref "J3") (pin "MH3") (pinfunction "MH3_MH3") (pintype "passive"))
    )
    (net (code "53") (name "unconnected-(J3-PadMH4)") (class "Default")
      (node (ref "J3") (pin "MH4") (pinfunction "MH4_MH4") (pintype "passive"))
    )
    (net (code "54") (name "unconnected-(J6-Pad1)") (class "Default")
      (node (ref "J6") (pin "1") (pinfunction "1_1") (pintype "passive"))
    )
    (net (code "55") (name "unconnected-(J6-Pad4)") (class "Default")
      (node (ref "J6") (pin "4") (pinfunction "4_4") (pintype "passive"))
    )
    (net (code "56") (name "unconnected-(J6-Pad6)") (class "Default")
      (node (ref "J6") (pin "6") (pinfunction "6_6") (pintype "passive"))
    )
    (net (code "57") (name "unconnected-(J6-Pad7)") (class "Default")
      (node (ref "J6") (pin "7") (pinfunction "7_7") (pintype "passive"))
    )
    (net (code "58") (name "unconnected-(J6-Pad8)") (class "Default")
      (node (ref "J6") (pin "8") (pinfunction "8_8") (pintype "passive"))
    )
    (net (code "59") (name "unconnected-(J6-Pad9)") (class "Default")
      (node (ref "J6") (pin "9") (pinfunction "9_9") (pintype "passive"))
    )
    (net (code "60") (name "unconnected-(J6-PadMH1)") (class "Default")
      (node (ref "J6") (pin "MH1") (pinfunction "MH1_MH1") (pintype "passive"))
    )
    (net (code "61") (name "unconnected-(J6-PadMH2)") (class "Default")
      (node (ref "J6") (pin "MH2") (pinfunction "MH2_MH2") (pintype "passive"))
    )
    (net (code "62") (name "unconnected-(RID-IRQ-Pad4)") (class "Default")
      (node (ref "RID") (pin "4") (pinfunction "IRQ_4") (pintype "output"))
    )
    (net (code "63") (name "unconnected-(S1-PadMH1)") (class "Default")
      (node (ref "S1") (pin "MH1") (pinfunction "MH1_MH1") (pintype "passive"))
    )
    (net (code "64") (name "unconnected-(S1-PadMH2)") (class "Default")
      (node (ref "S1") (pin "MH2") (pinfunction "MH2_MH2") (pintype "passive"))
    )
    (net (code "65") (name "unconnected-(U1-DIO0-Pad14)") (class "Default")
      (node (ref "U1") (pin "14") (pinfunction "DIO0_14") (pintype "bidirectional"))
    )
    (net (code "66") (name "unconnected-(U1-DIO1-Pad15)") (class "Default")
      (node (ref "U1") (pin "15") (pinfunction "DIO1_15") (pintype "bidirectional"))
    )
    (net (code "67") (name "unconnected-(U1-DIO2-Pad16)") (class "Default")
      (node (ref "U1") (pin "16") (pinfunction "DIO2_16") (pintype "bidirectional"))
    )
    (net (code "68") (name "unconnected-(U1-DIO3-Pad11)") (class "Default")
      (node (ref "U1") (pin "11") (pinfunction "DIO3_11") (pintype "bidirectional"))
    )
    (net (code "69") (name "unconnected-(U1-DIO4-Pad12)") (class "Default")
      (node (ref "U1") (pin "12") (pinfunction "DIO4_12") (pintype "bidirectional"))
    )
    (net (code "70") (name "unconnected-(U1-DIO5-Pad7)") (class "Default")
      (node (ref "U1") (pin "7") (pinfunction "DIO5_7") (pintype "bidirectional"))
    )
    (net (code "71") (name "unconnected-(U1-GND-Pad10)") (class "Default")
      (node (ref "U1") (pin "10") (pinfunction "GND_10") (pintype "power_in"))
    )
    (net (code "72") (name "unconnected-(U2-CLK-PadJ3-19)") (class "Default")
      (node (ref "U2") (pin "J3-19") (pinfunction "CLK_J3-19") (pintype "input"))
    )
    (net (code "73") (name "unconnected-(U2-CMD-PadJ2-18)") (class "Default")
      (node (ref "U2") (pin "J2-18") (pinfunction "CMD_J2-18") (pintype "bidirectional"))
    )
    (net (code "74") (name "unconnected-(U2-EN-PadJ2-2)") (class "Default")
      (node (ref "U2") (pin "J2-2") (pinfunction "EN_J2-2") (pintype "input"))
    )
    (net (code "75") (name "unconnected-(U2-IO0-PadJ3-14)") (class "Default")
      (node (ref "U2") (pin "J3-14") (pinfunction "IO0_J3-14") (pintype "bidirectional"))
    )
    (net (code "76") (name "unconnected-(U2-IO2-PadJ3-15)") (class "Default")
      (node (ref "U2") (pin "J3-15") (pinfunction "IO2_J3-15") (pintype "bidirectional"))
    )
    (net (code "77") (name "unconnected-(U2-IO35-PadJ2-6)") (class "Default")
      (node (ref "U2") (pin "J2-6") (pinfunction "IO35_J2-6") (pintype "bidirectional"))
    )
    (net (code "78") (name "unconnected-(U2-SD0-PadJ3-18)") (class "Default")
      (node (ref "U2") (pin "J3-18") (pinfunction "SD0_J3-18") (pintype "bidirectional"))
    )
    (net (code "79") (name "unconnected-(U2-SD1-PadJ3-17)") (class "Default")
      (node (ref "U2") (pin "J3-17") (pinfunction "SD1_J3-17") (pintype "bidirectional"))
    )
    (net (code "80") (name "unconnected-(U2-SD2-PadJ2-16)") (class "Default")
      (node (ref "U2") (pin "J2-16") (pinfunction "SD2_J2-16") (pintype "bidirectional"))
    )
    (net (code "81") (name "unconnected-(U2-SD3-PadJ2-17)") (class "Default")
      (node (ref "U2") (pin "J2-17") (pinfunction "SD3_J2-17") (pintype "bidirectional"))
    )
    (net (code "82") (name "unconnected-(U5-C2+-Pad4)") (class "Default")
      (node (ref "U5") (pin "4") (pinfunction "C2+_4") (pintype "passive"))
    )
    (net (code "83") (name "unconnected-(U5-C2--Pad5)") (class "Default")
      (node (ref "U5") (pin "5") (pinfunction "C2-_5") (pintype "passive"))
    )
    (net (code "84") (name "unconnected-(U5-DIN1-Pad11)") (class "Default")
      (node (ref "U5") (pin "11") (pinfunction "DIN1_11") (pintype "passive"))
    )
    (net (code "85") (name "unconnected-(U5-DOUT1-Pad14)") (class "Default")
      (node (ref "U5") (pin "14") (pinfunction "DOUT1_14") (pintype "passive"))
    )
    (net (code "86") (name "unconnected-(U5-RIN1-Pad13)") (class "Default")
      (node (ref "U5") (pin "13") (pinfunction "RIN1_13") (pintype "passive"))
    )
    (net (code "87") (name "unconnected-(U5-ROUT1-Pad12)") (class "Default")
      (node (ref "U5") (pin "12") (pinfunction "ROUT1_12") (pintype "passive"))
    )
  )
)
